# Schematic_sheet.net
KiCad netlist of a schematic drawn in Altium Designer
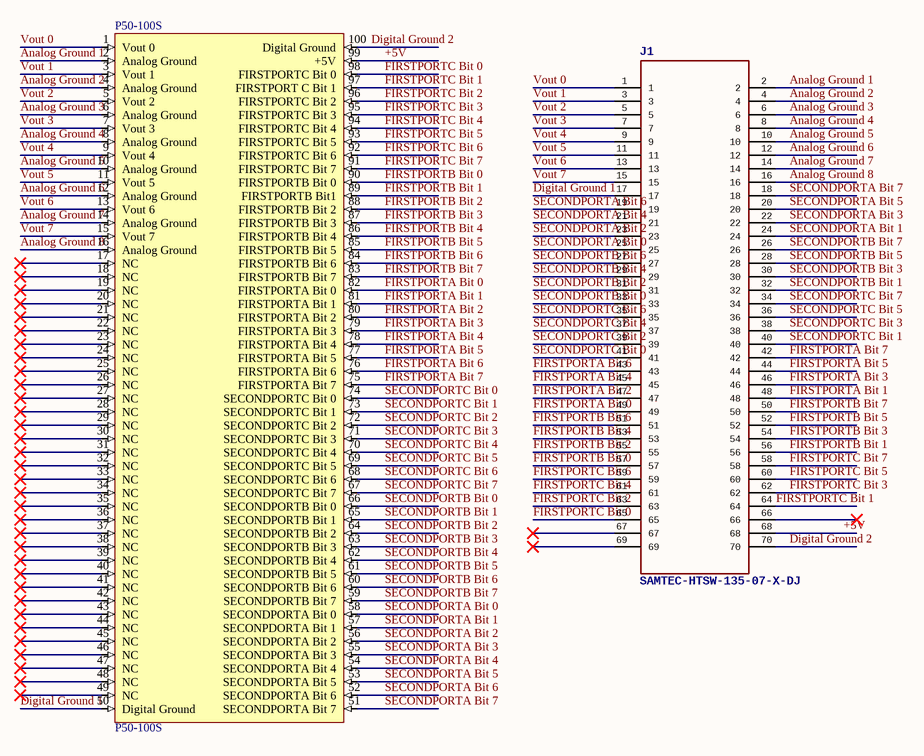
[diagram p0: Schematic sheet.SchDoc]

(export (version "E")
  (design (tool "Eeschema 10.0.6"))
  (components
    (comp (ref "J1")
      (value "SAMTEC-HTSW-135-07-X-DJ")
      (footprint "SAMTEC-HTSW-135-07-X-D")
      (libsource (lib "SAMTEC-HTSW-135-07-X-D") (part "SAMTEC-HTSW-135-07-X-DJ"))
    )
    (comp (ref "P50-100S")
      (value "P50-100S")
      (footprint "P50-100S-R1-EA")
      (libsource (lib "Schematic Library") (part "P50-100S"))
    )
  )
  (nets
    (net (code "1") (name "/+5V") (class "Default")
      (node (ref "J1") (pin "68") (pinfunction "68_68") (pintype "passive"))
      (node (ref "P50-100S") (pin "99") (pinfunction "+5V_99") (pintype "input"))
    )
    (net (code "2") (name "/Analog Ground 1") (class "Default")
      (node (ref "J1") (pin "2") (pinfunction "2_2") (pintype "passive"))
      (node (ref "P50-100S") (pin "2") (pinfunction "Analog_Ground_2") (pintype "input"))
    )
    (net (code "3") (name "/Analog Ground 2") (class "Default")
      (node (ref "J1") (pin "4") (pinfunction "4_4") (pintype "passive"))
      (node (ref "P50-100S") (pin "4") (pinfunction "Analog_Ground_4") (pintype "input"))
    )
    (net (code "4") (name "/Analog Ground 3") (class "Default")
      (node (ref "J1") (pin "6") (pinfunction "6_6") (pintype "passive"))
      (node (ref "P50-100S") (pin "6") (pinfunction "Analog_Ground_6") (pintype "input"))
    )
    (net (code "5") (name "/Analog Ground 4") (class "Default")
      (node (ref "J1") (pin "8") (pinfunction "8_8") (pintype "passive"))
      (node (ref "P50-100S") (pin "8") (pinfunction "Analog_Ground_8") (pintype "input"))
    )
    (net (code "6") (name "/Analog Ground 5") (class "Default")
      (node (ref "J1") (pin "10") (pinfunction "10_10") (pintype "passive"))
      (node (ref "P50-100S") (pin "10") (pinfunction "Analog_Ground_10") (pintype "input"))
    )
    (net (code "7") (name "/Analog Ground 6") (class "Default")
      (node (ref "J1") (pin "12") (pinfunction "12_12") (pintype "passive"))
      (node (ref "P50-100S") (pin "12") (pinfunction "Analog_Ground_12") (pintype "input"))
    )
    (net (code "8") (name "/Analog Ground 7") (class "Default")
      (node (ref "J1") (pin "14") (pinfunction "14_14") (pintype "passive"))
      (node (ref "P50-100S") (pin "14") (pinfunction "Analog_Ground_14") (pintype "input"))
    )
    (net (code "9") (name "/Analog Ground 8") (class "Default")
      (node (ref "J1") (pin "16") (pinfunction "16_16") (pintype "passive"))
      (node (ref "P50-100S") (pin "16") (pinfunction "Analog_Ground_16") (pintype "input"))
    )
    (net (code "10") (name "/Digital Ground 1") (class "Default")
      (node (ref "J1") (pin "17") (pinfunction "17_17") (pintype "passive"))
      (node (ref "P50-100S") (pin "50") (pinfunction "Digital_Ground_50") (pintype "input"))
    )
    (net (code "11") (name "/Digital Ground 2") (class "Default")
      (node (ref "J1") (pin "70") (pinfunction "70_70") (pintype "passive"))
      (node (ref "P50-100S") (pin "100") (pinfunction "Digital_Ground_100") (pintype "input"))
    )
    (net (code "12") (name "/FIRSTPORTA Bit 0") (class "Default")
      (node (ref "J1") (pin "49") (pinfunction "49_49") (pintype "passive"))
      (node (ref "P50-100S") (pin "82") (pinfunction "FIRSTPORTA_Bit_0_82") (pintype "input"))
    )
    (net (code "13") (name "/FIRSTPORTA Bit 1") (class "Default")
      (node (ref "J1") (pin "48") (pinfunction "48_48") (pintype "passive"))
      (node (ref "P50-100S") (pin "81") (pinfunction "FIRSTPORTA_Bit_1_81") (pintype "input"))
    )
    (net (code "14") (name "/FIRSTPORTA Bit 2") (class "Default")
      (node (ref "J1") (pin "47") (pinfunction "47_47") (pintype "passive"))
      (node (ref "P50-100S") (pin "80") (pinfunction "FIRSTPORTA_Bit_2_80") (pintype "input"))
    )
    (net (code "15") (name "/FIRSTPORTA Bit 3") (class "Default")
      (node (ref "J1") (pin "46") (pinfunction "46_46") (pintype "passive"))
      (node (ref "P50-100S") (pin "79") (pinfunction "FIRSTPORTA_Bit_3_79") (pintype "input"))
    )
    (net (code "16") (name "/FIRSTPORTA Bit 4") (class "Default")
      (node (ref "J1") (pin "45") (pinfunction "45_45") (pintype "passive"))
      (node (ref "P50-100S") (pin "78") (pinfunction "FIRSTPORTA_Bit_4_78") (pintype "input"))
    )
    (net (code "17") (name "/FIRSTPORTA Bit 5") (class "Default")
      (node (ref "J1") (pin "44") (pinfunction "44_44") (pintype "passive"))
      (node (ref "P50-100S") (pin "77") (pinfunction "FIRSTPORTA_Bit_5_77") (pintype "input"))
    )
    (net (code "18") (name "/FIRSTPORTA Bit 6") (class "Default")
      (node (ref "J1") (pin "43") (pinfunction "43_43") (pintype "passive"))
      (node (ref "P50-100S") (pin "76") (pinfunction "FIRSTPORTA_Bit_6_76") (pintype "input"))
    )
    (net (code "19") (name "/FIRSTPORTA Bit 7") (class "Default")
      (node (ref "J1") (pin "42") (pinfunction "42_42") (pintype "passive"))
      (node (ref "P50-100S") (pin "75") (pinfunction "FIRSTPORTA_Bit_7_75") (pintype "input"))
    )
    (net (code "20") (name "/FIRSTPORTB Bit 0") (class "Default")
      (node (ref "J1") (pin "57") (pinfunction "57_57") (pintype "passive"))
      (node (ref "P50-100S") (pin "90") (pinfunction "FIRSTPORTB_Bit_0_90") (pintype "input"))
    )
    (net (code "21") (name "/FIRSTPORTB Bit 1") (class "Default")
      (node (ref "J1") (pin "56") (pinfunction "56_56") (pintype "passive"))
      (node (ref "P50-100S") (pin "89") (pinfunction "FIRSTPORTB_Bit1_89") (pintype "input"))
    )
    (net (code "22") (name "/FIRSTPORTB Bit 2") (class "Default")
      (node (ref "J1") (pin "55") (pinfunction "55_55") (pintype "passive"))
      (node (ref "P50-100S") (pin "88") (pinfunction "FIRSTPORTB_Bit_2_88") (pintype "input"))
    )
    (net (code "23") (name "/FIRSTPORTB Bit 3") (class "Default")
      (node (ref "J1") (pin "54") (pinfunction "54_54") (pintype "passive"))
      (node (ref "P50-100S") (pin "87") (pinfunction "FIRSTPORTB_Bit_3_87") (pintype "input"))
    )
    (net (code "24") (name "/FIRSTPORTB Bit 4") (class "Default")
      (node (ref "J1") (pin "53") (pinfunction "53_53") (pintype "passive"))
      (node (ref "P50-100S") (pin "86") (pinfunction "FIRSTPORTB_Bit_4_86") (pintype "input"))
    )
    (net (code "25") (name "/FIRSTPORTB Bit 5") (class "Default")
      (node (ref "J1") (pin "52") (pinfunction "52_52") (pintype "passive"))
      (node (ref "P50-100S") (pin "85") (pinfunction "FIRSTPORTB_Bit_5_85") (pintype "input"))
    )
    (net (code "26") (name "/FIRSTPORTB Bit 6") (class "Default")
      (node (ref "J1") (pin "51") (pinfunction "51_51") (pintype "passive"))
      (node (ref "P50-100S") (pin "84") (pinfunction "FIRSTPORTB_Bit_6_84") (pintype "input"))
    )
    (net (code "27") (name "/FIRSTPORTB Bit 7") (class "Default")
      (node (ref "J1") (pin "50") (pinfunction "50_50") (pintype "passive"))
      (node (ref "P50-100S") (pin "83") (pinfunction "FIRSTPORTB_Bit_7_83") (pintype "input"))
    )
    (net (code "28") (name "/FIRSTPORTC Bit 0") (class "Default")
      (node (ref "J1") (pin "65") (pinfunction "65_65") (pintype "passive"))
      (node (ref "P50-100S") (pin "98") (pinfunction "FIRSTPORTC_Bit_0_98") (pintype "input"))
    )
    (net (code "29") (name "/FIRSTPORTC Bit 1") (class "Default")
      (node (ref "J1") (pin "64") (pinfunction "64_64") (pintype "passive"))
      (node (ref "P50-100S") (pin "97") (pinfunction "FIRSTPORT_C_Bit_1_97") (pintype "input"))
    )
    (net (code "30") (name "/FIRSTPORTC Bit 2") (class "Default")
      (node (ref "J1") (pin "63") (pinfunction "63_63") (pintype "passive"))
      (node (ref "P50-100S") (pin "96") (pinfunction "FIRSTPORTC_Bit_2_96") (pintype "input"))
    )
    (net (code "31") (name "/FIRSTPORTC Bit 3") (class "Default")
      (node (ref "J1") (pin "62") (pinfunction "62_62") (pintype "passive"))
      (node (ref "P50-100S") (pin "95") (pinfunction "FIRSTPORTC_Bit_3_95") (pintype "input"))
    )
    (net (code "32") (name "/FIRSTPORTC Bit 4") (class "Default")
      (node (ref "J1") (pin "61") (pinfunction "61_61") (pintype "passive"))
      (node (ref "P50-100S") (pin "94") (pinfunction "FIRSTPORTC_Bit_4_94") (pintype "input"))
    )
    (net (code "33") (name "/FIRSTPORTC Bit 5") (class "Default")
      (node (ref "J1") (pin "60") (pinfunction "60_60") (pintype "passive"))
      (node (ref "P50-100S") (pin "93") (pinfunction "FIRSTPORTC_Bit_5_93") (pintype "input"))
    )
    (net (code "34") (name "/FIRSTPORTC Bit 6") (class "Default")
      (node (ref "J1") (pin "59") (pinfunction "59_59") (pintype "passive"))
      (node (ref "P50-100S") (pin "92") (pinfunction "FIRSTPORTC_Bit_6_92") (pintype "input"))
    )
    (net (code "35") (name "/FIRSTPORTC Bit 7") (class "Default")
      (node (ref "J1") (pin "58") (pinfunction "58_58") (pintype "passive"))
      (node (ref "P50-100S") (pin "91") (pinfunction "FIRSTPORTC_Bit_7_91") (pintype "input"))
    )
    (net (code "36") (name "/SECONDPORTA Bit 0") (class "Default")
      (node (ref "J1") (pin "25") (pinfunction "25_25") (pintype "passive"))
      (node (ref "P50-100S") (pin "58") (pinfunction "SECONDPORTA_Bit_0_58") (pintype "input"))
    )
    (net (code "37") (name "/SECONDPORTA Bit 1") (class "Default")
      (node (ref "J1") (pin "24") (pinfunction "24_24") (pintype "passive"))
      (node (ref "P50-100S") (pin "57") (pinfunction "SECONPDORTA_Bit_1_57") (pintype "input"))
    )
    (net (code "38") (name "/SECONDPORTA Bit 2") (class "Default")
      (node (ref "J1") (pin "23") (pinfunction "23_23") (pintype "passive"))
      (node (ref "P50-100S") (pin "56") (pinfunction "SECONDPORTA_Bit_2_56") (pintype "input"))
    )
    (net (code "39") (name "/SECONDPORTA Bit 3") (class "Default")
      (node (ref "J1") (pin "22") (pinfunction "22_22") (pintype "passive"))
      (node (ref "P50-100S") (pin "55") (pinfunction "SECONDPORTA_Bit_3_55") (pintype "input"))
    )
    (net (code "40") (name "/SECONDPORTA Bit 4") (class "Default")
      (node (ref "J1") (pin "21") (pinfunction "21_21") (pintype "passive"))
      (node (ref "P50-100S") (pin "54") (pinfunction "SECONDPORTA_Bit_4_54") (pintype "input"))
    )
    (net (code "41") (name "/SECONDPORTA Bit 5") (class "Default")
      (node (ref "J1") (pin "20") (pinfunction "20_20") (pintype "passive"))
      (node (ref "P50-100S") (pin "53") (pinfunction "SECONDPORTA_Bit_5_53") (pintype "input"))
    )
    (net (code "42") (name "/SECONDPORTA Bit 6") (class "Default")
      (node (ref "J1") (pin "19") (pinfunction "19_19") (pintype "passive"))
      (node (ref "P50-100S") (pin "52") (pinfunction "SECONDPORTA_Bit_6_52") (pintype "input"))
    )
    (net (code "43") (name "/SECONDPORTA Bit 7") (class "Default")
      (node (ref "J1") (pin "18") (pinfunction "18_18") (pintype "passive"))
      (node (ref "P50-100S") (pin "51") (pinfunction "SECONDPORTA_Bit_7_51") (pintype "input"))
    )
    (net (code "44") (name "/SECONDPORTB Bit 0") (class "Default")
      (node (ref "J1") (pin "33") (pinfunction "33_33") (pintype "passive"))
      (node (ref "P50-100S") (pin "66") (pinfunction "SECONDPORTB_Bit_0_66") (pintype "input"))
    )
    (net (code "45") (name "/SECONDPORTB Bit 1") (class "Default")
      (node (ref "J1") (pin "32") (pinfunction "32_32") (pintype "passive"))
      (node (ref "P50-100S") (pin "65") (pinfunction "SECONDPORTB_Bit_1_65") (pintype "input"))
    )
    (net (code "46") (name "/SECONDPORTB Bit 2") (class "Default")
      (node (ref "J1") (pin "31") (pinfunction "31_31") (pintype "passive"))
      (node (ref "P50-100S") (pin "64") (pinfunction "SECONDPORTB_Bit_2_64") (pintype "input"))
    )
    (net (code "47") (name "/SECONDPORTB Bit 3") (class "Default")
      (node (ref "J1") (pin "30") (pinfunction "30_30") (pintype "passive"))
      (node (ref "P50-100S") (pin "63") (pinfunction "SECONDPORTB_Bit_3_63") (pintype "input"))
    )
    (net (code "48") (name "/SECONDPORTB Bit 4") (class "Default")
      (node (ref "J1") (pin "29") (pinfunction "29_29") (pintype "passive"))
      (node (ref "P50-100S") (pin "62") (pinfunction "SECONDPORTB_Bit_4_62") (pintype "input"))
    )
    (net (code "49") (name "/SECONDPORTB Bit 5") (class "Default")
      (node (ref "J1") (pin "28") (pinfunction "28_28") (pintype "passive"))
      (node (ref "P50-100S") (pin "61") (pinfunction "SECONDPORTB_Bit_5_61") (pintype "input"))
    )
    (net (code "50") (name "/SECONDPORTB Bit 6") (class "Default")
      (node (ref "J1") (pin "27") (pinfunction "27_27") (pintype "passive"))
      (node (ref "P50-100S") (pin "60") (pinfunction "SECONDPORTB_Bit_6_60") (pintype "input"))
    )
    (net (code "51") (name "/SECONDPORTB Bit 7") (class "Default")
      (node (ref "J1") (pin "26") (pinfunction "26_26") (pintype "passive"))
      (node (ref "P50-100S") (pin "59") (pinfunction "SECONDPORTB_Bit_7_59") (pintype "input"))
    )
    (net (code "52") (name "/SECONDPORTC Bit 0") (class "Default")
      (node (ref "J1") (pin "41") (pinfunction "41_41") (pintype "passive"))
      (node (ref "P50-100S") (pin "74") (pinfunction "SECONDPORTC_Bit_0_74") (pintype "input"))
    )
    (net (code "53") (name "/SECONDPORTC Bit 1") (class "Default")
      (node (ref "J1") (pin "40") (pinfunction "40_40") (pintype "passive"))
      (node (ref "P50-100S") (pin "73") (pinfunction "SECONDPORTC_Bit_1_73") (pintype "input"))
    )
    (net (code "54") (name "/SECONDPORTC Bit 2") (class "Default")
      (node (ref "J1") (pin "39") (pinfunction "39_39") (pintype "passive"))
      (node (ref "P50-100S") (pin "72") (pinfunction "SECONDPORTC_Bit_2_72") (pintype "input"))
    )
    (net (code "55") (name "/SECONDPORTC Bit 3") (class "Default")
      (node (ref "J1") (pin "38") (pinfunction "38_38") (pintype "passive"))
      (node (ref "P50-100S") (pin "71") (pinfunction "SECONDPORTC_Bit_3_71") (pintype "input"))
    )
    (net (code "56") (name "/SECONDPORTC Bit 4") (class "Default")
      (node (ref "J1") (pin "37") (pinfunction "37_37") (pintype "passive"))
      (node (ref "P50-100S") (pin "70") (pinfunction "SECONDPORTC_Bit_4_70") (pintype "input"))
    )
    (net (code "57") (name "/SECONDPORTC Bit 5") (class "Default")
      (node (ref "J1") (pin "36") (pinfunction "36_36") (pintype "passive"))
      (node (ref "P50-100S") (pin "69") (pinfunction "SECONDPORTC_Bit_5_69") (pintype "input"))
    )
    (net (code "58") (name "/SECONDPORTC Bit 6") (class "Default")
      (node (ref "J1") (pin "35") (pinfunction "35_35") (pintype "passive"))
      (node (ref "P50-100S") (pin "68") (pinfunction "SECONDPORTC_Bit_6_68") (pintype "input"))
    )
    (net (code "59") (name "/SECONDPORTC Bit 7") (class "Default")
      (node (ref "J1") (pin "34") (pinfunction "34_34") (pintype "passive"))
      (node (ref "P50-100S") (pin "67") (pinfunction "SECONDPORTC_Bit_7_67") (pintype "input"))
    )
    (net (code "60") (name "/Vout 0") (class "Default")
      (node (ref "J1") (pin "1") (pinfunction "1_1") (pintype "passive"))
      (node (ref "P50-100S") (pin "1") (pinfunction "Vout_0_1") (pintype "input"))
    )
    (net (code "61") (name "/Vout 1") (class "Default")
      (node (ref "J1") (pin "3") (pinfunction "3_3") (pintype "passive"))
      (node (ref "P50-100S") (pin "3") (pinfunction "Vout_1_3") (pintype "input"))
    )
    (net (code "62") (name "/Vout 2") (class "Default")
      (node (ref "J1") (pin "5") (pinfunction "5_5") (pintype "passive"))
      (node (ref "P50-100S") (pin "5") (pinfunction "Vout_2_5") (pintype "input"))
    )
    (net (code "63") (name "/Vout 3") (class "Default")
      (node (ref "J1") (pin "7") (pinfunction "7_7") (pintype "passive"))
      (node (ref "P50-100S") (pin "7") (pinfunction "Vout_3_7") (pintype "input"))
    )
    (net (code "64") (name "/Vout 4") (class "Default")
      (node (ref "J1") (pin "9") (pinfunction "9_9") (pintype "passive"))
      (node (ref "P50-100S") (pin "9") (pinfunction "Vout_4_9") (pintype "input"))
    )
    (net (code "65") (name "/Vout 5") (class "Default")
      (node (ref "J1") (pin "11") (pinfunction "11_11") (pintype "passive"))
      (node (ref "P50-100S") (pin "11") (pinfunction "Vout_5_11") (pintype "input"))
    )
    (net (code "66") (name "/Vout 6") (class "Default")
      (node (ref "J1") (pin "13") (pinfunction "13_13") (pintype "passive"))
      (node (ref "P50-100S") (pin "13") (pinfunction "Vout_6_13") (pintype "input"))
    )
    (net (code "67") (name "/Vout 7") (class "Default")
      (node (ref "J1") (pin "15") (pinfunction "15_15") (pintype "passive"))
      (node (ref "P50-100S") (pin "15") (pinfunction "Vout_7_15") (pintype "input"))
    )
    (net (code "68") (name "unconnected-(J1-Pad66)") (class "Default")
      (node (ref "J1") (pin "66") (pinfunction "66_66") (pintype "passive+no_connect"))
    )
    (net (code "69") (name "unconnected-(J1-Pad67)") (class "Default")
      (node (ref "J1") (pin "67") (pinfunction "67_67") (pintype "passive+no_connect"))
    )
    (net (code "70") (name "unconnected-(J1-Pad69)") (class "Default")
      (node (ref "J1") (pin "69") (pinfunction "69_69") (pintype "passive+no_connect"))
    )
    (net (code "71") (name "unconnected-(P50-100S-NC-Pad17)") (class "Default")
      (node (ref "P50-100S") (pin "17") (pinfunction "NC_17") (pintype "input+no_connect"))
    )
    (net (code "72") (name "unconnected-(P50-100S-NC-Pad18)") (class "Default")
      (node (ref "P50-100S") (pin "18") (pinfunction "NC_18") (pintype "input+no_connect"))
    )
    (net (code "73") (name "unconnected-(P50-100S-NC-Pad19)") (class "Default")
      (node (ref "P50-100S") (pin "19") (pinfunction "NC_19") (pintype "input+no_connect"))
    )
    (net (code "74") (name "unconnected-(P50-100S-NC-Pad20)") (class "Default")
      (node (ref "P50-100S") (pin "20") (pinfunction "NC_20") (pintype "input+no_connect"))
    )
    (net (code "75") (name "unconnected-(P50-100S-NC-Pad21)") (class "Default")
      (node (ref "P50-100S") (pin "21") (pinfunction "NC_21") (pintype "input+no_connect"))
    )
    (net (code "76") (name "unconnected-(P50-100S-NC-Pad22)") (class "Default")
      (node (ref "P50-100S") (pin "22") (pinfunction "NC_22") (pintype "input+no_connect"))
    )
    (net (code "77") (name "unconnected-(P50-100S-NC-Pad23)") (class "Default")
      (node (ref "P50-100S") (pin "23") (pinfunction "NC_23") (pintype "input+no_connect"))
    )
    (net (code "78") (name "unconnected-(P50-100S-NC-Pad24)") (class "Default")
      (node (ref "P50-100S") (pin "24") (pinfunction "NC_24") (pintype "input+no_connect"))
    )
    (net (code "79") (name "unconnected-(P50-100S-NC-Pad25)") (class "Default")
      (node (ref "P50-100S") (pin "25") (pinfunction "NC_25") (pintype "input+no_connect"))
    )
    (net (code "80") (name "unconnected-(P50-100S-NC-Pad26)") (class "Default")
      (node (ref "P50-100S") (pin "26") (pinfunction "NC_26") (pintype "input+no_connect"))
    )
    (net (code "81") (name "unconnected-(P50-100S-NC-Pad27)") (class "Default")
      (node (ref "P50-100S") (pin "27") (pinfunction "NC_27") (pintype "input+no_connect"))
    )
    (net (code "82") (name "unconnected-(P50-100S-NC-Pad28)") (class "Default")
      (node (ref "P50-100S") (pin "28") (pinfunction "NC_28") (pintype "input+no_connect"))
    )
    (net (code "83") (name "unconnected-(P50-100S-NC-Pad29)") (class "Default")
      (node (ref "P50-100S") (pin "29") (pinfunction "NC_29") (pintype "input+no_connect"))
    )
    (net (code "84") (name "unconnected-(P50-100S-NC-Pad30)") (class "Default")
      (node (ref "P50-100S") (pin "30") (pinfunction "NC_30") (pintype "input+no_connect"))
    )
    (net (code "85") (name "unconnected-(P50-100S-NC-Pad31)") (class "Default")
      (node (ref "P50-100S") (pin "31") (pinfunction "NC_31") (pintype "input+no_connect"))
    )
    (net (code "86") (name "unconnected-(P50-100S-NC-Pad32)") (class "Default")
      (node (ref "P50-100S") (pin "32") (pinfunction "NC_32") (pintype "input+no_connect"))
    )
    (net (code "87") (name "unconnected-(P50-100S-NC-Pad33)") (class "Default")
      (node (ref "P50-100S") (pin "33") (pinfunction "NC_33") (pintype "input+no_connect"))
    )
    (net (code "88") (name "unconnected-(P50-100S-NC-Pad34)") (class "Default")
      (node (ref "P50-100S") (pin "34") (pinfunction "NC_34") (pintype "input+no_connect"))
    )
    (net (code "89") (name "unconnected-(P50-100S-NC-Pad35)") (class "Default")
      (node (ref "P50-100S") (pin "35") (pinfunction "NC_35") (pintype "input+no_connect"))
    )
    (net (code "90") (name "unconnected-(P50-100S-NC-Pad36)") (class "Default")
      (node (ref "P50-100S") (pin "36") (pinfunction "NC_36") (pintype "input+no_connect"))
    )
    (net (code "91") (name "unconnected-(P50-100S-NC-Pad37)") (class "Default")
      (node (ref "P50-100S") (pin "37") (pinfunction "NC_37") (pintype "input+no_connect"))
    )
    (net (code "92") (name "unconnected-(P50-100S-NC-Pad38)") (class "Default")
      (node (ref "P50-100S") (pin "38") (pinfunction "NC_38") (pintype "input+no_connect"))
    )
    (net (code "93") (name "unconnected-(P50-100S-NC-Pad39)") (class "Default")
      (node (ref "P50-100S") (pin "39") (pinfunction "NC_39") (pintype "input+no_connect"))
    )
    (net (code "94") (name "unconnected-(P50-100S-NC-Pad40)") (class "Default")
      (node (ref "P50-100S") (pin "40") (pinfunction "NC_40") (pintype "input+no_connect"))
    )
    (net (code "95") (name "unconnected-(P50-100S-NC-Pad41)") (class "Default")
      (node (ref "P50-100S") (pin "41") (pinfunction "NC_41") (pintype "input+no_connect"))
    )
    (net (code "96") (name "unconnected-(P50-100S-NC-Pad42)") (class "Default")
      (node (ref "P50-100S") (pin "42") (pinfunction "NC_42") (pintype "input+no_connect"))
    )
    (net (code "97") (name "unconnected-(P50-100S-NC-Pad43)") (class "Default")
      (node (ref "P50-100S") (pin "43") (pinfunction "NC_43") (pintype "input+no_connect"))
    )
    (net (code "98") (name "unconnected-(P50-100S-NC-Pad44)") (class "Default")
      (node (ref "P50-100S") (pin "44") (pinfunction "NC_44") (pintype "input+no_connect"))
    )
    (net (code "99") (name "unconnected-(P50-100S-NC-Pad45)") (class "Default")
      (node (ref "P50-100S") (pin "45") (pinfunction "NC_45") (pintype "input+no_connect"))
    )
    (net (code "100") (name "unconnected-(P50-100S-NC-Pad46)") (class "Default")
      (node (ref "P50-100S") (pin "46") (pinfunction "NC_46") (pintype "input+no_connect"))
    )
    (net (code "101") (name "unconnected-(P50-100S-NC-Pad47)") (class "Default")
      (node (ref "P50-100S") (pin "47") (pinfunction "NC_47") (pintype "input+no_connect"))
    )
    (net (code "102") (name "unconnected-(P50-100S-NC-Pad48)") (class "Default")
      (node (ref "P50-100S") (pin "48") (pinfunction "NC_48") (pintype "input+no_connect"))
    )
    (net (code "103") (name "unconnected-(P50-100S-NC-Pad49)") (class "Default")
      (node (ref "P50-100S") (pin "49") (pinfunction "NC_49") (pintype "input+no_connect"))
    )
  )
)
